# levelshifter.net
KiCad netlist of a schematic drawn in EAGLE
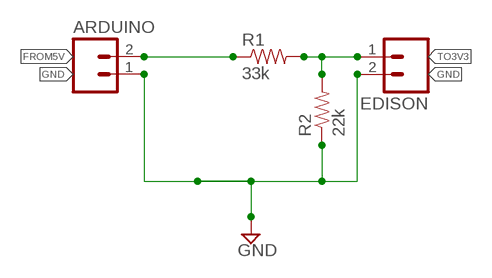
[diagram p0: schematic, sheet 1]

(export (version "E")
  (design (tool "Eeschema 10.0.6"))
  (components
    (comp (ref "ARDUINO")
      (value "M02PTH3")
      (footprint "eagle-import:1X02_LONGPADS")
      (libsource (lib "eagle-import") (part "M02PTH3"))
    )
    (comp (ref "EDISON")
      (value "M02PTH3")
      (footprint "eagle-import:1X02_LONGPADS")
      (libsource (lib "eagle-import") (part "M02PTH3"))
    )
    (comp (ref "R1")
      (value "33k")
      (footprint "eagle-import:AXIAL-0.3")
      (libsource (lib "eagle-import") (part "RESISTORAXIAL-0.3"))
    )
    (comp (ref "R2")
      (value "22k")
      (footprint "eagle-import:AXIAL-0.3")
      (libsource (lib "eagle-import") (part "RESISTORAXIAL-0.3"))
    )
  )
  (nets
    (net (code "1") (name "FROM5V") (class "Default")
      (node (ref "ARDUINO") (pin "2") (pinfunction "2_2") (pintype "passive"))
      (node (ref "R1") (pin "P$1") (pinfunction "1_P$1") (pintype "passive"))
    )
    (net (code "2") (name "GND") (class "Default")
      (node (ref "ARDUINO") (pin "1") (pinfunction "1_1") (pintype "passive"))
      (node (ref "EDISON") (pin "2") (pinfunction "2_2") (pintype "passive"))
      (node (ref "R2") (pin "P$1") (pinfunction "1_P$1") (pintype "passive"))
    )
    (net (code "3") (name "TO3V3") (class "Default")
      (node (ref "EDISON") (pin "1") (pinfunction "1_1") (pintype "passive"))
      (node (ref "R1") (pin "P$2") (pinfunction "2_P$2") (pintype "passive"))
      (node (ref "R2") (pin "P$2") (pinfunction "2_P$2") (pintype "passive"))
    )
  )
)
